# video.net
KiCad netlist of a schematic drawn in Altium Designer
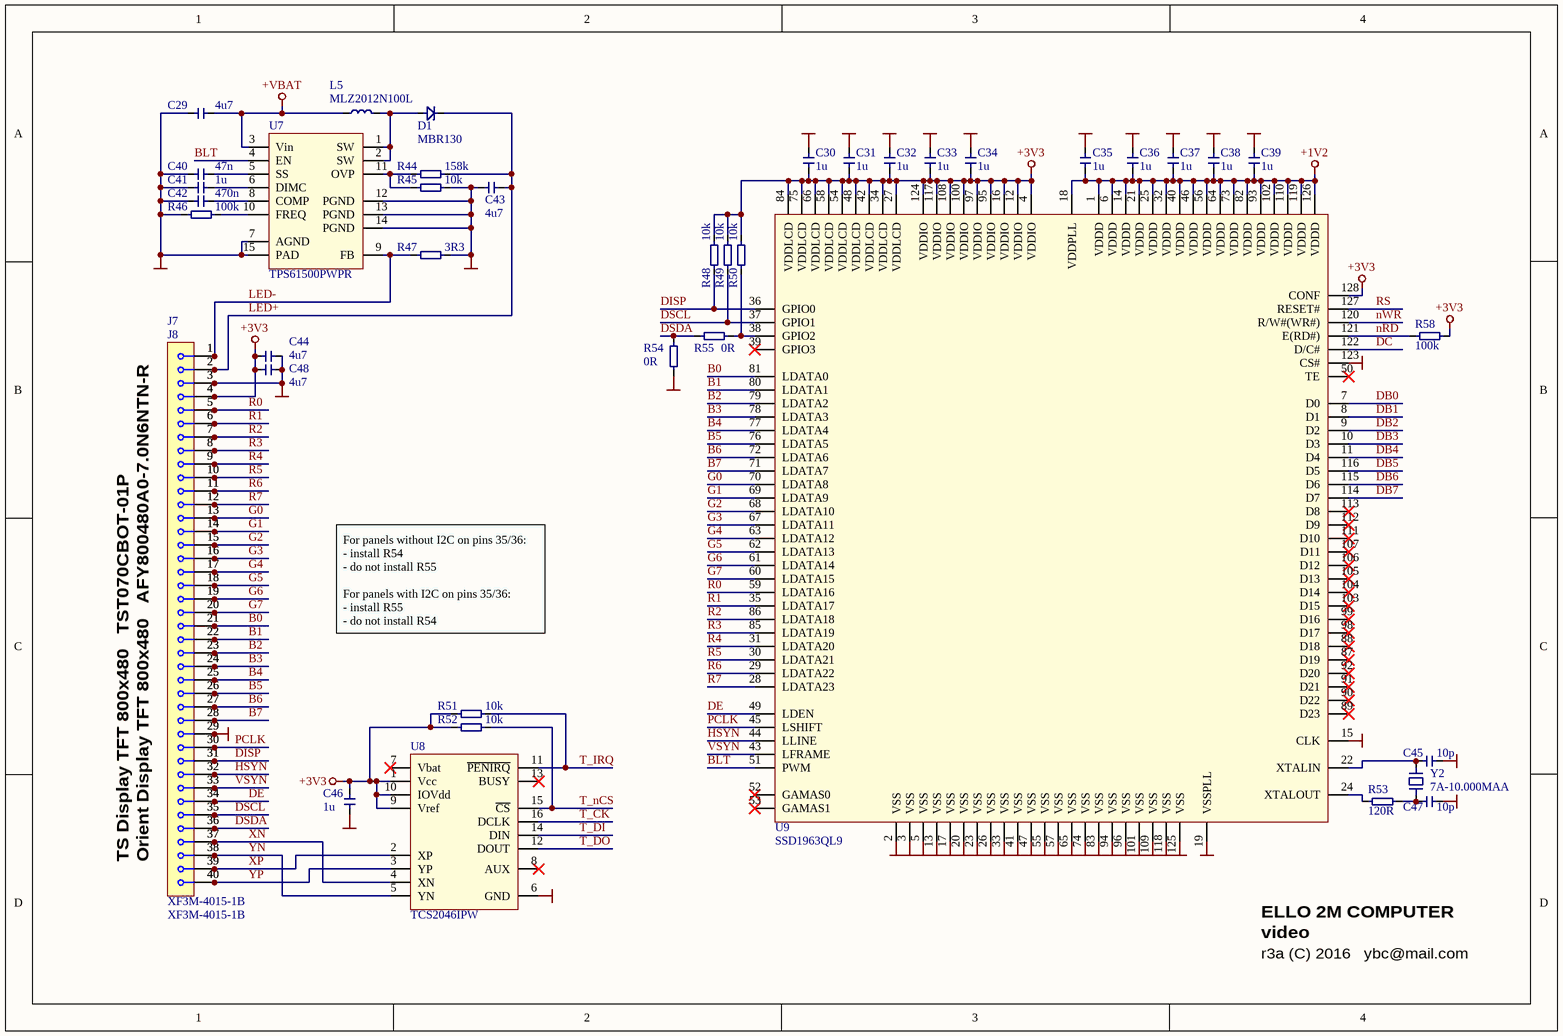
[diagram p0: video.SchDoc]

(export (version "E")
  (design (tool "Eeschema 10.0.6"))
  (components
    (comp (ref "C29")
      (value "4u7")
      (footprint "_1206")
      (description "Capacitor")
      (libsource (lib "Discretes") (part "Capacitor"))
    )
    (comp (ref "C30")
      (value "1u")
      (footprint "_0603")
      (description "Capacitor")
      (libsource (lib "Discretes") (part "Capacitor"))
    )
    (comp (ref "C31")
      (value "1u")
      (footprint "_0603")
      (description "Capacitor")
      (libsource (lib "Discretes") (part "Capacitor"))
    )
    (comp (ref "C32")
      (value "1u")
      (footprint "_0603")
      (description "Capacitor")
      (libsource (lib "Discretes") (part "Capacitor"))
    )
    (comp (ref "C33")
      (value "1u")
      (footprint "_0603")
      (description "Capacitor")
      (libsource (lib "Discretes") (part "Capacitor"))
    )
    (comp (ref "C34")
      (value "1u")
      (footprint "_0603")
      (description "Capacitor")
      (libsource (lib "Discretes") (part "Capacitor"))
    )
    (comp (ref "C35")
      (value "1u")
      (footprint "_0603")
      (description "Capacitor")
      (libsource (lib "Discretes") (part "Capacitor"))
    )
    (comp (ref "C36")
      (value "1u")
      (footprint "_0603")
      (description "Capacitor")
      (libsource (lib "Discretes") (part "Capacitor"))
    )
    (comp (ref "C37")
      (value "1u")
      (footprint "_0603")
      (description "Capacitor")
      (libsource (lib "Discretes") (part "Capacitor"))
    )
    (comp (ref "C38")
      (value "1u")
      (footprint "_0603")
      (description "Capacitor")
      (libsource (lib "Discretes") (part "Capacitor"))
    )
    (comp (ref "C39")
      (value "1u")
      (footprint "_0603")
      (description "Capacitor")
      (libsource (lib "Discretes") (part "Capacitor"))
    )
    (comp (ref "C40")
      (value "47n")
      (footprint "_0603")
      (description "Capacitor")
      (libsource (lib "Discretes") (part "Capacitor"))
    )
    (comp (ref "C41")
      (value "1u")
      (footprint "_0603")
      (description "Capacitor")
      (libsource (lib "Discretes") (part "Capacitor"))
    )
    (comp (ref "C42")
      (value "470n")
      (footprint "_0603")
      (description "Capacitor")
      (libsource (lib "Discretes") (part "Capacitor"))
    )
    (comp (ref "C43")
      (value "4u7")
      (footprint "_1206")
      (description "Capacitor")
      (libsource (lib "Discretes") (part "Capacitor"))
    )
    (comp (ref "C44")
      (value "4u7")
      (footprint "_1206")
      (description "Capacitor")
      (libsource (lib "Discretes") (part "Capacitor"))
    )
    (comp (ref "C45")
      (value "10p")
      (footprint "_0603")
      (description "Capacitor")
      (libsource (lib "Discretes") (part "Capacitor"))
    )
    (comp (ref "C46")
      (value "1u")
      (footprint "_0603")
      (description "Capacitor")
      (libsource (lib "Discretes") (part "Capacitor"))
    )
    (comp (ref "C47")
      (value "10p")
      (footprint "_0603")
      (description "Capacitor")
      (libsource (lib "Discretes") (part "Capacitor"))
    )
    (comp (ref "C48")
      (value "4u7")
      (footprint "_1206")
      (description "Capacitor")
      (libsource (lib "Discretes") (part "Capacitor"))
    )
    (comp (ref "D1")
      (value "MBR130")
      (footprint "SOD-123")
      (description "Schottky diode")
      (libsource (lib "Discretes") (part "Diode Schottky"))
    )
    (comp (ref "J7")
      (value "XF3M-4015-1B")
      (footprint "XF3M-4015-1B")
      (description "Single row, 40-way connector")
      (libsource (lib "Connectors") (part "Connector 1x40"))
    )
    (comp (ref "J8")
      (value "XF3M-4015-1B")
      (footprint "XF3M-4015-1B")
      (description "Single row, 40-way connector")
      (libsource (lib "Connectors") (part "Connector 1x40"))
    )
    (comp (ref "L5")
      (value "MLZ2012N100L")
      (footprint "_0805_IND")
      (description "Inductor")
      (libsource (lib "Discretes") (part "Inductor"))
    )
    (comp (ref "R44")
      (value "158k")
      (footprint "_0603")
      (description "Resistor")
      (libsource (lib "Discretes") (part "Resistor"))
    )
    (comp (ref "R45")
      (value "10k")
      (footprint "_0603")
      (description "Resistor")
      (libsource (lib "Discretes") (part "Resistor"))
    )
    (comp (ref "R46")
      (value "100k")
      (footprint "_0603")
      (description "Resistor")
      (libsource (lib "") (part "Resistor_1"))
    )
    (comp (ref "R47")
      (value "3R3")
      (footprint "_1206")
      (description "Resistor")
      (libsource (lib "") (part "Resistor_1"))
    )
    (comp (ref "R48")
      (value "10k")
      (footprint "_0603")
      (description "Resistor")
      (libsource (lib "") (part "Resistor_2"))
    )
    (comp (ref "R49")
      (value "10k")
      (footprint "_0603")
      (description "Resistor")
      (libsource (lib "") (part "Resistor_2"))
    )
    (comp (ref "R50")
      (value "10k")
      (footprint "_0603")
      (description "Resistor")
      (libsource (lib "") (part "Resistor_2"))
    )
    (comp (ref "R51")
      (value "10k")
      (footprint "_0603")
      (description "Resistor")
      (libsource (lib "") (part "Resistor_1"))
    )
    (comp (ref "R52")
      (value "10k")
      (footprint "_0603")
      (description "Resistor")
      (libsource (lib "") (part "Resistor_1"))
    )
    (comp (ref "R53")
      (value "120R")
      (footprint "_0603")
      (description "Resistor")
      (libsource (lib "") (part "Resistor_1"))
    )
    (comp (ref "R54")
      (value "0R")
      (footprint "_0603")
      (description "Resistor")
      (libsource (lib "") (part "Resistor_3"))
    )
    (comp (ref "R55")
      (value "0R")
      (footprint "_0603")
      (description "Resistor")
      (libsource (lib "") (part "Resistor_1"))
    )
    (comp (ref "R58")
      (value "100k")
      (footprint "_0603")
      (description "Resistor")
      (libsource (lib "Discretes") (part "Resistor"))
    )
    (comp (ref "U7")
      (value "TPS61500PWPR")
      (footprint "TSOP65P650X110_HS-14N")
      (description "TPS61500 3-A Boost Converter for High Brightness  LED Driver With Multiple Dimming Methods")
      (fields (field (name "MANUFACTURER") "Texas Instruments"))
      (libsource (lib "IC Drivers and Switches") (part "TPS61500"))
    )
    (comp (ref "U8")
      (value "TCS2046IPW")
      (footprint "SOP65P640X120-16N")
      (fields (field (name "MANUFACTURER") "Shenzhen XPTEK Technology"))
      (libsource (lib "IC Other Functions") (part "XPT2046 (TSOP16)"))
    )
    (comp (ref "U9")
      (value "SSD1963QL9")
      (footprint "SQFP40P1600X1600-128N")
      (description "1215KB Embedded Display SRAM LCD Display Controller")
      (fields (field (name "MANUFACTURER") "Solomon Systech"))
      (libsource (lib "IC Audio and Video") (part "SSD1963Q"))
    )
    (comp (ref "Y2")
      (value "7A-10.000MAA")
      (footprint "Crystal 50x32 (2)")
      (description "Crystal Resonator")
      (libsource (lib "Discretes") (part "Crystal"))
    )
  )
  (nets
    (net (code "1") (name "+1V2") (class "Default")
      (node (ref "C35") (pin "2") (pintype "passive"))
      (node (ref "C36") (pin "2") (pintype "passive"))
      (node (ref "C37") (pin "2") (pintype "passive"))
      (node (ref "C38") (pin "2") (pintype "passive"))
      (node (ref "C39") (pin "2") (pintype "passive"))
      (node (ref "U9") (pin "1") (pinfunction "VDDD_1") (pintype "passive"))
      (node (ref "U9") (pin "102") (pinfunction "VDDD_102") (pintype "passive"))
      (node (ref "U9") (pin "110") (pinfunction "VDDD_110") (pintype "passive"))
      (node (ref "U9") (pin "119") (pinfunction "VDDD_119") (pintype "passive"))
      (node (ref "U9") (pin "126") (pinfunction "VDDD_126") (pintype "passive"))
      (node (ref "U9") (pin "14") (pinfunction "VDDD_14") (pintype "passive"))
      (node (ref "U9") (pin "18") (pinfunction "VDDPLL_18") (pintype "passive"))
      (node (ref "U9") (pin "21") (pinfunction "VDDD_21") (pintype "passive"))
      (node (ref "U9") (pin "25") (pinfunction "VDDD_25") (pintype "passive"))
      (node (ref "U9") (pin "32") (pinfunction "VDDD_32") (pintype "passive"))
      (node (ref "U9") (pin "40") (pinfunction "VDDD_40") (pintype "passive"))
      (node (ref "U9") (pin "46") (pinfunction "VDDD_46") (pintype "passive"))
      (node (ref "U9") (pin "56") (pinfunction "VDDD_56") (pintype "passive"))
      (node (ref "U9") (pin "6") (pinfunction "VDDD_6") (pintype "passive"))
      (node (ref "U9") (pin "64") (pinfunction "VDDD_64") (pintype "passive"))
      (node (ref "U9") (pin "73") (pinfunction "VDDD_73") (pintype "passive"))
      (node (ref "U9") (pin "82") (pinfunction "VDDD_82") (pintype "passive"))
      (node (ref "U9") (pin "93") (pinfunction "VDDD_93") (pintype "passive"))
    )
    (net (code "2") (name "+3V3") (class "Default")
      (node (ref "C30") (pin "2") (pintype "passive"))
      (node (ref "C31") (pin "2") (pintype "passive"))
      (node (ref "C32") (pin "2") (pintype "passive"))
      (node (ref "C33") (pin "2") (pintype "passive"))
      (node (ref "C34") (pin "2") (pintype "passive"))
      (node (ref "C44") (pin "2") (pintype "passive"))
      (node (ref "C46") (pin "1") (pintype "passive"))
      (node (ref "C48") (pin "2") (pintype "passive"))
      (node (ref "J7") (pin "4") (pinfunction "4_4") (pintype "passive"))
      (node (ref "J8") (pin "4") (pinfunction "4_4") (pintype "passive"))
      (node (ref "R48") (pin "2") (pintype "passive"))
      (node (ref "R49") (pin "2") (pintype "passive"))
      (node (ref "R50") (pin "2") (pintype "passive"))
      (node (ref "R51") (pin "2") (pintype "passive"))
      (node (ref "R52") (pin "2") (pintype "passive"))
      (node (ref "R58") (pin "2") (pintype "passive"))
      (node (ref "U8") (pin "1") (pinfunction "Vcc_1") (pintype "passive"))
      (node (ref "U8") (pin "10") (pinfunction "IOVdd_10") (pintype "passive"))
      (node (ref "U8") (pin "9") (pinfunction "Vref_9") (pintype "passive"))
      (node (ref "U9") (pin "100") (pinfunction "VDDIO_100") (pintype "passive"))
      (node (ref "U9") (pin "108") (pinfunction "VDDIO_108") (pintype "passive"))
      (node (ref "U9") (pin "117") (pinfunction "VDDIO_117") (pintype "passive"))
      (node (ref "U9") (pin "12") (pinfunction "VDDIO_12") (pintype "passive"))
      (node (ref "U9") (pin "124") (pinfunction "VDDIO_124") (pintype "passive"))
      (node (ref "U9") (pin "128") (pinfunction "CONF_128") (pintype "passive"))
      (node (ref "U9") (pin "16") (pinfunction "VDDIO_16") (pintype "passive"))
      (node (ref "U9") (pin "27") (pinfunction "VDDLCD_27") (pintype "passive"))
      (node (ref "U9") (pin "34") (pinfunction "VDDLCD_34") (pintype "passive"))
      (node (ref "U9") (pin "4") (pinfunction "VDDIO_4") (pintype "passive"))
      (node (ref "U9") (pin "42") (pinfunction "VDDLCD_42") (pintype "passive"))
      (node (ref "U9") (pin "48") (pinfunction "VDDLCD_48") (pintype "passive"))
      (node (ref "U9") (pin "54") (pinfunction "VDDLCD_54") (pintype "passive"))
      (node (ref "U9") (pin "58") (pinfunction "VDDLCD_58") (pintype "passive"))
      (node (ref "U9") (pin "66") (pinfunction "VDDLCD_66") (pintype "passive"))
      (node (ref "U9") (pin "75") (pinfunction "VDDLCD_75") (pintype "passive"))
      (node (ref "U9") (pin "84") (pinfunction "VDDLCD_84") (pintype "passive"))
      (node (ref "U9") (pin "95") (pinfunction "VDDIO_95") (pintype "passive"))
      (node (ref "U9") (pin "97") (pinfunction "VDDIO_97") (pintype "passive"))
    )
    (net (code "3") (name "+VBAT") (class "Default")
      (node (ref "C29") (pin "1") (pintype "passive"))
      (node (ref "L5") (pin "1") (pintype "passive"))
      (node (ref "U7") (pin "3") (pinfunction "Vin_3") (pintype "passive"))
    )
    (net (code "4") (name "/B0") (class "Default")
      (node (ref "J7") (pin "21") (pinfunction "21_21") (pintype "passive"))
      (node (ref "J8") (pin "21") (pinfunction "21_21") (pintype "passive"))
      (node (ref "U9") (pin "81") (pinfunction "LDATA0_81") (pintype "passive"))
    )
    (net (code "5") (name "/B1") (class "Default")
      (node (ref "J7") (pin "22") (pinfunction "22_22") (pintype "passive"))
      (node (ref "J8") (pin "22") (pinfunction "22_22") (pintype "passive"))
      (node (ref "U9") (pin "80") (pinfunction "LDATA1_80") (pintype "passive"))
    )
    (net (code "6") (name "/B2") (class "Default")
      (node (ref "J7") (pin "23") (pinfunction "23_23") (pintype "passive"))
      (node (ref "J8") (pin "23") (pinfunction "23_23") (pintype "passive"))
      (node (ref "U9") (pin "79") (pinfunction "LDATA2_79") (pintype "passive"))
    )
    (net (code "7") (name "/B3") (class "Default")
      (node (ref "J7") (pin "24") (pinfunction "24_24") (pintype "passive"))
      (node (ref "J8") (pin "24") (pinfunction "24_24") (pintype "passive"))
      (node (ref "U9") (pin "78") (pinfunction "LDATA3_78") (pintype "passive"))
    )
    (net (code "8") (name "/B4") (class "Default")
      (node (ref "J7") (pin "25") (pinfunction "25_25") (pintype "passive"))
      (node (ref "J8") (pin "25") (pinfunction "25_25") (pintype "passive"))
      (node (ref "U9") (pin "77") (pinfunction "LDATA4_77") (pintype "passive"))
    )
    (net (code "9") (name "/B5") (class "Default")
      (node (ref "J7") (pin "26") (pinfunction "26_26") (pintype "passive"))
      (node (ref "J8") (pin "26") (pinfunction "26_26") (pintype "passive"))
      (node (ref "U9") (pin "76") (pinfunction "LDATA5_76") (pintype "passive"))
    )
    (net (code "10") (name "/B6") (class "Default")
      (node (ref "J7") (pin "27") (pinfunction "27_27") (pintype "passive"))
      (node (ref "J8") (pin "27") (pinfunction "27_27") (pintype "passive"))
      (node (ref "U9") (pin "72") (pinfunction "LDATA6_72") (pintype "passive"))
    )
    (net (code "11") (name "/B7") (class "Default")
      (node (ref "J7") (pin "28") (pinfunction "28_28") (pintype "passive"))
      (node (ref "J8") (pin "28") (pinfunction "28_28") (pintype "passive"))
      (node (ref "U9") (pin "71") (pinfunction "LDATA7_71") (pintype "passive"))
    )
    (net (code "12") (name "/BLT") (class "Default")
      (node (ref "U7") (pin "4") (pinfunction "EN_4") (pintype "passive"))
      (node (ref "U9") (pin "51") (pinfunction "PWM_51") (pintype "passive"))
    )
    (net (code "13") (name "/DB0") (class "Default")
      (node (ref "U9") (pin "7") (pinfunction "D0_7") (pintype "passive"))
    )
    (net (code "14") (name "/DB1") (class "Default")
      (node (ref "U9") (pin "8") (pinfunction "D1_8") (pintype "passive"))
    )
    (net (code "15") (name "/DB2") (class "Default")
      (node (ref "U9") (pin "9") (pinfunction "D2_9") (pintype "passive"))
    )
    (net (code "16") (name "/DB3") (class "Default")
      (node (ref "U9") (pin "10") (pinfunction "D3_10") (pintype "passive"))
    )
    (net (code "17") (name "/DB4") (class "Default")
      (node (ref "U9") (pin "11") (pinfunction "D4_11") (pintype "passive"))
    )
    (net (code "18") (name "/DB5") (class "Default")
      (node (ref "U9") (pin "116") (pinfunction "D5_116") (pintype "passive"))
    )
    (net (code "19") (name "/DB6") (class "Default")
      (node (ref "U9") (pin "115") (pinfunction "D6_115") (pintype "passive"))
    )
    (net (code "20") (name "/DB7") (class "Default")
      (node (ref "U9") (pin "114") (pinfunction "D7_114") (pintype "passive"))
    )
    (net (code "21") (name "/DC") (class "Default")
      (node (ref "U9") (pin "122") (pinfunction "D/C#_122") (pintype "passive"))
    )
    (net (code "22") (name "/DE") (class "Default")
      (node (ref "J7") (pin "34") (pinfunction "34_34") (pintype "passive"))
      (node (ref "J8") (pin "34") (pinfunction "34_34") (pintype "passive"))
      (node (ref "U9") (pin "49") (pinfunction "LDEN_49") (pintype "passive"))
    )
    (net (code "23") (name "/DISP") (class "Default")
      (node (ref "J7") (pin "31") (pinfunction "31_31") (pintype "passive"))
      (node (ref "J8") (pin "31") (pinfunction "31_31") (pintype "passive"))
      (node (ref "R48") (pin "1") (pintype "passive"))
      (node (ref "U9") (pin "36") (pinfunction "GPIO0_36") (pintype "passive"))
    )
    (net (code "24") (name "/DSCL") (class "Default")
      (node (ref "J7") (pin "35") (pinfunction "35_35") (pintype "passive"))
      (node (ref "J8") (pin "35") (pinfunction "35_35") (pintype "passive"))
      (node (ref "R49") (pin "1") (pintype "passive"))
      (node (ref "U9") (pin "37") (pinfunction "GPIO1_37") (pintype "passive"))
    )
    (net (code "25") (name "/DSDA") (class "Default")
      (node (ref "J7") (pin "36") (pinfunction "36_36") (pintype "passive"))
      (node (ref "J8") (pin "36") (pinfunction "36_36") (pintype "passive"))
      (node (ref "R54") (pin "1") (pintype "passive"))
      (node (ref "R55") (pin "2") (pintype "passive"))
    )
    (net (code "26") (name "/G0") (class "Default")
      (node (ref "J7") (pin "13") (pinfunction "13_13") (pintype "passive"))
      (node (ref "J8") (pin "13") (pinfunction "13_13") (pintype "passive"))
      (node (ref "U9") (pin "70") (pinfunction "LDATA8_70") (pintype "passive"))
    )
    (net (code "27") (name "/G1") (class "Default")
      (node (ref "J7") (pin "14") (pinfunction "14_14") (pintype "passive"))
      (node (ref "J8") (pin "14") (pinfunction "14_14") (pintype "passive"))
      (node (ref "U9") (pin "69") (pinfunction "LDATA9_69") (pintype "passive"))
    )
    (net (code "28") (name "/G2") (class "Default")
      (node (ref "J7") (pin "15") (pinfunction "15_15") (pintype "passive"))
      (node (ref "J8") (pin "15") (pinfunction "15_15") (pintype "passive"))
      (node (ref "U9") (pin "68") (pinfunction "LDATA10_68") (pintype "passive"))
    )
    (net (code "29") (name "/G3") (class "Default")
      (node (ref "J7") (pin "16") (pinfunction "16_16") (pintype "passive"))
      (node (ref "J8") (pin "16") (pinfunction "16_16") (pintype "passive"))
      (node (ref "U9") (pin "67") (pinfunction "LDATA11_67") (pintype "passive"))
    )
    (net (code "30") (name "/G4") (class "Default")
      (node (ref "J7") (pin "17") (pinfunction "17_17") (pintype "passive"))
      (node (ref "J8") (pin "17") (pinfunction "17_17") (pintype "passive"))
      (node (ref "U9") (pin "63") (pinfunction "LDATA12_63") (pintype "passive"))
    )
    (net (code "31") (name "/G5") (class "Default")
      (node (ref "J7") (pin "18") (pinfunction "18_18") (pintype "passive"))
      (node (ref "J8") (pin "18") (pinfunction "18_18") (pintype "passive"))
      (node (ref "U9") (pin "62") (pinfunction "LDATA13_62") (pintype "passive"))
    )
    (net (code "32") (name "/G6") (class "Default")
      (node (ref "J7") (pin "19") (pinfunction "19_19") (pintype "passive"))
      (node (ref "J8") (pin "19") (pinfunction "19_19") (pintype "passive"))
      (node (ref "U9") (pin "61") (pinfunction "LDATA14_61") (pintype "passive"))
    )
    (net (code "33") (name "/G7") (class "Default")
      (node (ref "J7") (pin "20") (pinfunction "20_20") (pintype "passive"))
      (node (ref "J8") (pin "20") (pinfunction "20_20") (pintype "passive"))
      (node (ref "U9") (pin "60") (pinfunction "LDATA15_60") (pintype "passive"))
    )
    (net (code "34") (name "/HSYN") (class "Default")
      (node (ref "J7") (pin "32") (pinfunction "32_32") (pintype "passive"))
      (node (ref "J8") (pin "32") (pinfunction "32_32") (pintype "passive"))
      (node (ref "U9") (pin "44") (pinfunction "LLINE_44") (pintype "passive"))
    )
    (net (code "35") (name "/LED+") (class "Default")
      (node (ref "C43") (pin "2") (pintype "passive"))
      (node (ref "D1") (pin "1") (pintype "passive"))
      (node (ref "J7") (pin "2") (pinfunction "2_2") (pintype "passive"))
      (node (ref "J8") (pin "2") (pinfunction "2_2") (pintype "passive"))
      (node (ref "R44") (pin "2") (pintype "passive"))
    )
    (net (code "36") (name "/LED-") (class "Default")
      (node (ref "J7") (pin "1") (pinfunction "1_1") (pintype "passive"))
      (node (ref "J8") (pin "1") (pinfunction "1_1") (pintype "passive"))
      (node (ref "R47") (pin "2") (pintype "passive"))
      (node (ref "U7") (pin "9") (pinfunction "FB_9") (pintype "passive"))
    )
    (net (code "37") (name "/PCLK") (class "Default")
      (node (ref "J7") (pin "30") (pinfunction "30_30") (pintype "passive"))
      (node (ref "J8") (pin "30") (pinfunction "30_30") (pintype "passive"))
      (node (ref "U9") (pin "45") (pinfunction "LSHIFT_45") (pintype "passive"))
    )
    (net (code "38") (name "/R0") (class "Default")
      (node (ref "J7") (pin "5") (pinfunction "5_5") (pintype "passive"))
      (node (ref "J8") (pin "5") (pinfunction "5_5") (pintype "passive"))
      (node (ref "U9") (pin "59") (pinfunction "LDATA16_59") (pintype "passive"))
    )
    (net (code "39") (name "/R1") (class "Default")
      (node (ref "J7") (pin "6") (pinfunction "6_6") (pintype "passive"))
      (node (ref "J8") (pin "6") (pinfunction "6_6") (pintype "passive"))
      (node (ref "U9") (pin "35") (pinfunction "LDATA17_35") (pintype "passive"))
    )
    (net (code "40") (name "/R2") (class "Default")
      (node (ref "J7") (pin "7") (pinfunction "7_7") (pintype "passive"))
      (node (ref "J8") (pin "7") (pinfunction "7_7") (pintype "passive"))
      (node (ref "U9") (pin "86") (pinfunction "LDATA18_86") (pintype "passive"))
    )
    (net (code "41") (name "/R3") (class "Default")
      (node (ref "J7") (pin "8") (pinfunction "8_8") (pintype "passive"))
      (node (ref "J8") (pin "8") (pinfunction "8_8") (pintype "passive"))
      (node (ref "U9") (pin "85") (pinfunction "LDATA19_85") (pintype "passive"))
    )
    (net (code "42") (name "/R4") (class "Default")
      (node (ref "J7") (pin "9") (pinfunction "9_9") (pintype "passive"))
      (node (ref "J8") (pin "9") (pinfunction "9_9") (pintype "passive"))
      (node (ref "U9") (pin "31") (pinfunction "LDATA20_31") (pintype "passive"))
    )
    (net (code "43") (name "/R5") (class "Default")
      (node (ref "J7") (pin "10") (pinfunction "10_10") (pintype "passive"))
      (node (ref "J8") (pin "10") (pinfunction "10_10") (pintype "passive"))
      (node (ref "U9") (pin "30") (pinfunction "LDATA21_30") (pintype "passive"))
    )
    (net (code "44") (name "/R6") (class "Default")
      (node (ref "J7") (pin "11") (pinfunction "11_11") (pintype "passive"))
      (node (ref "J8") (pin "11") (pinfunction "11_11") (pintype "passive"))
      (node (ref "U9") (pin "29") (pinfunction "LDATA22_29") (pintype "passive"))
    )
    (net (code "45") (name "/R7") (class "Default")
      (node (ref "J7") (pin "12") (pinfunction "12_12") (pintype "passive"))
      (node (ref "J8") (pin "12") (pinfunction "12_12") (pintype "passive"))
      (node (ref "U9") (pin "28") (pinfunction "LDATA23_28") (pintype "passive"))
    )
    (net (code "46") (name "/RS") (class "Default")
      (node (ref "U9") (pin "127") (pinfunction "RESET#_127") (pintype "passive"))
    )
    (net (code "47") (name "/T_CK") (class "Default")
      (node (ref "U8") (pin "16") (pinfunction "DCLK_16") (pintype "passive"))
    )
    (net (code "48") (name "/T_DI") (class "Default")
      (node (ref "U8") (pin "14") (pinfunction "DIN_14") (pintype "passive"))
    )
    (net (code "49") (name "/T_DO") (class "Default")
      (node (ref "U8") (pin "12") (pinfunction "DOUT_12") (pintype "passive"))
    )
    (net (code "50") (name "/T_IRQ") (class "Default")
      (node (ref "R51") (pin "1") (pintype "passive"))
      (node (ref "U8") (pin "11") (pinfunction "~{PENIRQ}_11") (pintype "passive"))
    )
    (net (code "51") (name "/T_nCS") (class "Default")
      (node (ref "R52") (pin "1") (pintype "passive"))
      (node (ref "U8") (pin "15") (pinfunction "~{CS}_15") (pintype "passive"))
    )
    (net (code "52") (name "/VSYN") (class "Default")
      (node (ref "J7") (pin "33") (pinfunction "33_33") (pintype "passive"))
      (node (ref "J8") (pin "33") (pinfunction "33_33") (pintype "passive"))
      (node (ref "U9") (pin "43") (pinfunction "LFRAME_43") (pintype "passive"))
    )
    (net (code "53") (name "/XN") (class "Default")
      (node (ref "J7") (pin "37") (pinfunction "37_37") (pintype "passive"))
      (node (ref "J8") (pin "37") (pinfunction "37_37") (pintype "passive"))
      (node (ref "U8") (pin "4") (pinfunction "XN_4") (pintype "passive"))
    )
    (net (code "54") (name "/XP") (class "Default")
      (node (ref "J7") (pin "39") (pinfunction "39_39") (pintype "passive"))
      (node (ref "J8") (pin "39") (pinfunction "39_39") (pintype "passive"))
      (node (ref "U8") (pin "2") (pinfunction "XP_2") (pintype "passive"))
    )
    (net (code "55") (name "/YN") (class "Default")
      (node (ref "J7") (pin "38") (pinfunction "38_38") (pintype "passive"))
      (node (ref "J8") (pin "38") (pinfunction "38_38") (pintype "passive"))
      (node (ref "U8") (pin "5") (pinfunction "YN_5") (pintype "passive"))
    )
    (net (code "56") (name "/YP") (class "Default")
      (node (ref "J7") (pin "40") (pinfunction "40_40") (pintype "passive"))
      (node (ref "J8") (pin "40") (pinfunction "40_40") (pintype "passive"))
      (node (ref "U8") (pin "3") (pinfunction "YP_3") (pintype "passive"))
    )
    (net (code "57") (name "/nRD") (class "Default")
      (node (ref "R58") (pin "1") (pintype "passive"))
      (node (ref "U9") (pin "121") (pinfunction "E(RD#)_121") (pintype "passive"))
    )
    (net (code "58") (name "/nWR") (class "Default")
      (node (ref "U9") (pin "120") (pinfunction "R/W#(WR#)_120") (pintype "passive"))
    )
    (net (code "59") (name "GND") (class "Default")
      (node (ref "C29") (pin "2") (pintype "passive"))
      (node (ref "C30") (pin "1") (pintype "passive"))
      (node (ref "C31") (pin "1") (pintype "passive"))
      (node (ref "C32") (pin "1") (pintype "passive"))
      (node (ref "C33") (pin "1") (pintype "passive"))
      (node (ref "C34") (pin "1") (pintype "passive"))
      (node (ref "C35") (pin "1") (pintype "passive"))
      (node (ref "C36") (pin "1") (pintype "passive"))
      (node (ref "C37") (pin "1") (pintype "passive"))
      (node (ref "C38") (pin "1") (pintype "passive"))
      (node (ref "C39") (pin "1") (pintype "passive"))
      (node (ref "C40") (pin "2") (pintype "passive"))
      (node (ref "C41") (pin "2") (pintype "passive"))
      (node (ref "C42") (pin "2") (pintype "passive"))
      (node (ref "C43") (pin "1") (pintype "passive"))
      (node (ref "C44") (pin "1") (pintype "passive"))
      (node (ref "C45") (pin "2") (pintype "passive"))
      (node (ref "C46") (pin "2") (pintype "passive"))
      (node (ref "C47") (pin "2") (pintype "passive"))
      (node (ref "C48") (pin "1") (pintype "passive"))
      (node (ref "J7") (pin "29") (pinfunction "29_29") (pintype "passive"))
      (node (ref "J7") (pin "3") (pinfunction "3_3") (pintype "passive"))
      (node (ref "J8") (pin "29") (pinfunction "29_29") (pintype "passive"))
      (node (ref "J8") (pin "3") (pinfunction "3_3") (pintype "passive"))
      (node (ref "R45") (pin "2") (pintype "passive"))
      (node (ref "R46") (pin "2") (pintype "passive"))
      (node (ref "R47") (pin "1") (pintype "passive"))
      (node (ref "R54") (pin "2") (pintype "passive"))
      (node (ref "U7") (pin "12") (pinfunction "PGND_12") (pintype "passive"))
      (node (ref "U7") (pin "13") (pinfunction "PGND_13") (pintype "passive"))
      (node (ref "U7") (pin "14") (pinfunction "PGND_14") (pintype "passive"))
      (node (ref "U7") (pin "15") (pinfunction "PAD_15") (pintype "passive"))
      (node (ref "U7") (pin "7") (pinfunction "AGND_7") (pintype "passive"))
      (node (ref "U8") (pin "6") (pinfunction "GND_6") (pintype "passive"))
      (node (ref "U9") (pin "101") (pinfunction "VSS_101") (pintype "passive"))
      (node (ref "U9") (pin "109") (pinfunction "VSS_109") (pintype "passive"))
      (node (ref "U9") (pin "118") (pinfunction "VSS_118") (pintype "passive"))
      (node (ref "U9") (pin "123") (pinfunction "CS#_123") (pintype "passive"))
      (node (ref "U9") (pin "125") (pinfunction "VSS_125") (pintype "passive"))
      (node (ref "U9") (pin "13") (pinfunction "VSS_13") (pintype "passive"))
      (node (ref "U9") (pin "15") (pinfunction "CLK_15") (pintype "passive"))
      (node (ref "U9") (pin "17") (pinfunction "VSS_17") (pintype "passive"))
      (node (ref "U9") (pin "19") (pinfunction "VSSPLL_19") (pintype "passive"))
      (node (ref "U9") (pin "2") (pinfunction "VSS_2") (pintype "passive"))
      (node (ref "U9") (pin "20") (pinfunction "VSS_20") (pintype "passive"))
      (node (ref "U9") (pin "23") (pinfunction "VSS_23") (pintype "passive"))
      (node (ref "U9") (pin "26") (pinfunction "VSS_26") (pintype "passive"))
      (node (ref "U9") (pin "3") (pinfunction "VSS_3") (pintype "passive"))
      (node (ref "U9") (pin "33") (pinfunction "VSS_33") (pintype "passive"))
      (node (ref "U9") (pin "41") (pinfunction "VSS_41") (pintype "passive"))
      (node (ref "U9") (pin "47") (pinfunction "VSS_47") (pintype "passive"))
      (node (ref "U9") (pin "5") (pinfunction "VSS_5") (pintype "passive"))
      (node (ref "U9") (pin "55") (pinfunction "VSS_55") (pintype "passive"))
      (node (ref "U9") (pin "57") (pinfunction "VSS_57") (pintype "passive"))
      (node (ref "U9") (pin "65") (pinfunction "VSS_65") (pintype "passive"))
      (node (ref "U9") (pin "74") (pinfunction "VSS_74") (pintype "passive"))
      (node (ref "U9") (pin "83") (pinfunction "VSS_83") (pintype "passive"))
      (node (ref "U9") (pin "94") (pinfunction "VSS_94") (pintype "passive"))
      (node (ref "U9") (pin "96") (pinfunction "VSS_96") (pintype "passive"))
    )
    (net (code "60") (name "Net-(C47-Pad1)") (class "Default")
      (node (ref "C47") (pin "1") (pintype "passive"))
      (node (ref "R53") (pin "1") (pintype "passive"))
      (node (ref "Y2") (pin "1") (pintype "passive"))
    )
    (net (code "61") (name "Net-(D1-Pad2)") (class "Default")
      (node (ref "D1") (pin "2") (pintype "passive"))
      (node (ref "L5") (pin "2") (pintype "passive"))
      (node (ref "U7") (pin "1") (pinfunction "SW_1") (pintype "passive"))
      (node (ref "U7") (pin "2") (pinfunction "SW_2") (pintype "passive"))
    )
    (net (code "62") (name "Net-(U7-COMP)") (class "Default")
      (node (ref "C42") (pin "1") (pintype "passive"))
      (node (ref "U7") (pin "8") (pinfunction "COMP_8") (pintype "passive"))
    )
    (net (code "63") (name "Net-(U7-DIMC)") (class "Default")
      (node (ref "C41") (pin "1") (pintype "passive"))
      (node (ref "U7") (pin "6") (pinfunction "DIMC_6") (pintype "passive"))
    )
    (net (code "64") (name "Net-(U7-FREQ)") (class "Default")
      (node (ref "R46") (pin "1") (pintype "passive"))
      (node (ref "U7") (pin "10") (pinfunction "FREQ_10") (pintype "passive"))
    )
    (net (code "65") (name "Net-(U7-OVP)") (class "Default")
      (node (ref "R44") (pin "1") (pintype "passive"))
      (node (ref "R45") (pin "1") (pintype "passive"))
      (node (ref "U7") (pin "11") (pinfunction "OVP_11") (pintype "passive"))
    )
    (net (code "66") (name "Net-(U7-SS)") (class "Default")
      (node (ref "C40") (pin "1") (pintype "passive"))
      (node (ref "U7") (pin "5") (pinfunction "SS_5") (pintype "passive"))
    )
    (net (code "67") (name "Net-(U9-GPIO2)") (class "Default")
      (node (ref "R50") (pin "1") (pintype "passive"))
      (node (ref "R55") (pin "1") (pintype "passive"))
      (node (ref "U9") (pin "38") (pinfunction "GPIO2_38") (pintype "passive"))
    )
    (net (code "68") (name "Net-(U9-XTALIN)") (class "Default")
      (node (ref "C45") (pin "1") (pintype "passive"))
      (node (ref "U9") (pin "22") (pinfunction "XTALIN_22") (pintype "passive"))
      (node (ref "Y2") (pin "2") (pintype "passive"))
    )
    (net (code "69") (name "Net-(U9-XTALOUT)") (class "Default")
      (node (ref "R53") (pin "2") (pintype "passive"))
      (node (ref "U9") (pin "24") (pinfunction "XTALOUT_24") (pintype "passive"))
    )
    (net (code "70") (name "unconnected-(U8-AUX-Pad8)") (class "Default")
      (node (ref "U8") (pin "8") (pinfunction "AUX_8") (pintype "passive+no_connect"))
    )
    (net (code "71") (name "unconnected-(U8-BUSY-Pad13)") (class "Default")
      (node (ref "U8") (pin "13") (pinfunction "BUSY_13") (pintype "passive+no_connect"))
    )
    (net (code "72") (name "unconnected-(U8-Vbat-Pad7)") (class "Default")
      (node (ref "U8") (pin "7") (pinfunction "Vbat_7") (pintype "passive+no_connect"))
    )
    (net (code "73") (name "unconnected-(U9-D8-Pad113)") (class "Default")
      (node (ref "U9") (pin "113") (pinfunction "D8_113") (pintype "passive+no_connect"))
    )
    (net (code "74") (name "unconnected-(U9-D9-Pad112)") (class "Default")
      (node (ref "U9") (pin "112") (pinfunction "D9_112") (pintype "passive+no_connect"))
    )
    (net (code "75") (name "unconnected-(U9-D10-Pad111)") (class "Default")
      (node (ref "U9") (pin "111") (pinfunction "D10_111") (pintype "passive+no_connect"))
    )
    (net (code "76") (name "unconnected-(U9-D11-Pad107)") (class "Default")
      (node (ref "U9") (pin "107") (pinfunction "D11_107") (pintype "passive+no_connect"))
    )
    (net (code "77") (name "unconnected-(U9-D12-Pad106)") (class "Default")
      (node (ref "U9") (pin "106") (pinfunction "D12_106") (pintype "passive+no_connect"))
    )
    (net (code "78") (name "unconnected-(U9-D13-Pad105)") (class "Default")
      (node (ref "U9") (pin "105") (pinfunction "D13_105") (pintype "passive+no_connect"))
    )
    (net (code "79") (name "unconnected-(U9-D14-Pad104)") (class "Default")
      (node (ref "U9") (pin "104") (pinfunction "D14_104") (pintype "passive+no_connect"))
    )
    (net (code "80") (name "unconnected-(U9-D15-Pad103)") (class "Default")
      (node (ref "U9") (pin "103") (pinfunction "D15_103") (pintype "passive+no_connect"))
    )
    (net (code "81") (name "unconnected-(U9-D16-Pad99)") (class "Default")
      (node (ref "U9") (pin "99") (pinfunction "D16_99") (pintype "passive+no_connect"))
    )
    (net (code "82") (name "unconnected-(U9-D17-Pad98)") (class "Default")
      (node (ref "U9") (pin "98") (pinfunction "D17_98") (pintype "passive+no_connect"))
    )
    (net (code "83") (name "unconnected-(U9-D18-Pad88)") (class "Default")
      (node (ref "U9") (pin "88") (pinfunction "D18_88") (pintype "passive+no_connect"))
    )
    (net (code "84") (name "unconnected-(U9-D19-Pad87)") (class "Default")
      (node (ref "U9") (pin "87") (pinfunction "D19_87") (pintype "passive+no_connect"))
    )
    (net (code "85") (name "unconnected-(U9-D20-Pad92)") (class "Default")
      (node (ref "U9") (pin "92") (pinfunction "D20_92") (pintype "passive+no_connect"))
    )
    (net (code "86") (name "unconnected-(U9-D21-Pad91)") (class "Default")
      (node (ref "U9") (pin "91") (pinfunction "D21_91") (pintype "passive+no_connect"))
    )
    (net (code "87") (name "unconnected-(U9-D22-Pad90)") (class "Default")
      (node (ref "U9") (pin "90") (pinfunction "D22_90") (pintype "passive+no_connect"))
    )
    (net (code "88") (name "unconnected-(U9-D23-Pad89)") (class "Default")
      (node (ref "U9") (pin "89") (pinfunction "D23_89") (pintype "passive+no_connect"))
    )
    (net (code "89") (name "unconnected-(U9-GAMAS0-Pad52)") (class "Default")
      (node (ref "U9") (pin "52") (pinfunction "GAMAS0_52") (pintype "passive+no_connect"))
    )
    (net (code "90") (name "unconnected-(U9-GAMAS1-Pad53)") (class "Default")
      (node (ref "U9") (pin "53") (pinfunction "GAMAS1_53") (pintype "passive+no_connect"))
    )
    (net (code "91") (name "unconnected-(U9-GPIO3-Pad39)") (class "Default")
      (node (ref "U9") (pin "39") (pinfunction "GPIO3_39") (pintype "passive+no_connect"))
    )
    (net (code "92") (name "unconnected-(U9-TE-Pad50)") (class "Default")
      (node (ref "U9") (pin "50") (pinfunction "TE_50") (pintype "passive+no_connect"))
    )
  )
)
